# OTP6_PingCircuit.net
KiCad netlist of a schematic drawn in Altium Designer
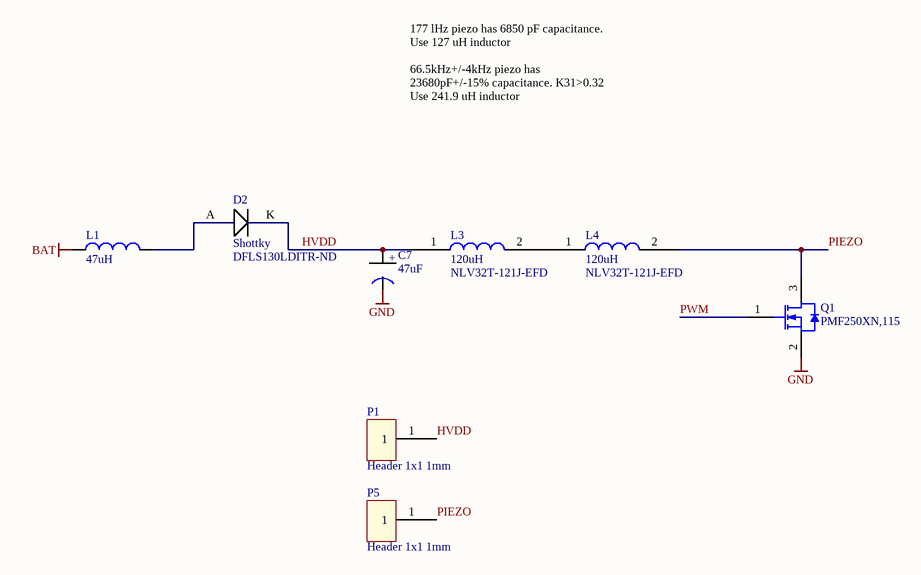
[diagram p0: OTP6_PingCircuit.SchDoc]

(export (version "E")
  (design (tool "Eeschema 10.0.6"))
  (components
    (comp (ref "C7") (value "47uF") (footprint "Tant0805") (libsource (lib "Loggerhead") (part "Tant0805")))
    (comp (ref "D2")
      (value "Shottky")
      (footprint "DFLS130")
      (fields (field (name "SUPPLIER PART NUMBER 1") "DFLS130LDITR-ND"))
      (libsource (lib "Loggerhead") (part "DFLS130"))
    )
    (comp (ref "L1")
      (value "47uH")
      (footprint "Inductor KLZ1608AHR")
      (libsource (lib "Loggerhead") (part "Inductor KLZ1608"))
    )
    (comp (ref "L3")
      (value "120uH")
      (footprint "Inductor_NLV32T")
      (fields (field (name "SUPPLIER PART NUMBER 1") "NLV32T-121J-EFD"))
      (libsource (lib "Loggerhead") (part "Inductor_NLV32T"))
    )
    (comp (ref "L4")
      (value "120uH")
      (footprint "Inductor_NLV32T")
      (fields (field (name "SUPPLIER PART NUMBER 1") "NLV32T-121J-EFD"))
      (libsource (lib "Loggerhead") (part "Inductor_NLV32T"))
    )
    (comp (ref "P1")
      (value "Header 1x1 1mm")
      (footprint "Header1x1mm")
      (description "1mm through hole")
      (libsource (lib "Loggerhead") (part "Header 1x1 1mm"))
    )
    (comp (ref "P5")
      (value "Header 1x1 1mm")
      (footprint "Header1x1mm")
      (description "1mm through hole")
      (libsource (lib "Loggerhead") (part "Header 1x1 1mm"))
    )
    (comp (ref "Q1")
      (value "PMF250XN,115")
      (footprint "NXP-SOT323_N")
      (description "N-Channel Trench MOSFET, 30 V, 0.9 A, -55 to 150 degC, 3-Pin SOT323, Tape and Reel")
      (fields (field (name "MANUFACTURER") "NXP Semiconductors"))
      (libsource (lib "NXP Semiconductors Standard MOSFETs") (part "PMF250XN,115"))
    )
  )
  (nets
    (net (code "1") (name "/HVDD") (class "Default")
      (node (ref "C7") (pin "2") (pinfunction "+_2") (pintype "passive"))
      (node (ref "D2") (pin "K") (pintype "passive"))
      (node (ref "L3") (pin "1") (pinfunction "1_1") (pintype "passive"))
      (node (ref "P1") (pin "1") (pinfunction "1_1") (pintype "passive"))
    )
    (net (code "2") (name "/PIEZO") (class "Default")
      (node (ref "L4") (pin "2") (pinfunction "2_2") (pintype "passive"))
      (node (ref "P5") (pin "1") (pinfunction "1_1") (pintype "passive"))
      (node (ref "Q1") (pin "3") (pinfunction "D_3") (pintype "passive"))
    )
    (net (code "3") (name "/PWM") (class "Default")
      (node (ref "Q1") (pin "1") (pinfunction "G_1") (pintype "passive"))
    )
    (net (code "4") (name "BAT") (class "Default")
      (node (ref "L1") (pin "1") (pinfunction "1_1") (pintype "passive"))
    )
    (net (code "5") (name "GND") (class "Default")
      (node (ref "C7") (pin "1") (pinfunction "GND_1") (pintype "passive"))
      (node (ref "Q1") (pin "2") (pinfunction "S_2") (pintype "passive"))
    )
    (net (code "6") (name "Net-(D2-PadA)") (class "Default")
      (node (ref "D2") (pin "A") (pintype "passive"))
      (node (ref "L1") (pin "2") (pinfunction "2_2") (pintype "passive"))
    )
    (net (code "7") (name "Net-(L3-Pad2)") (class "Default")
      (node (ref "L3") (pin "2") (pinfunction "2_2") (pintype "passive"))
      (node (ref "L4") (pin "1") (pinfunction "1_1") (pintype "passive"))
    )
  )
)
